# SAMD_Arduino_1.net
KiCad netlist of a schematic drawn in Altium Designer
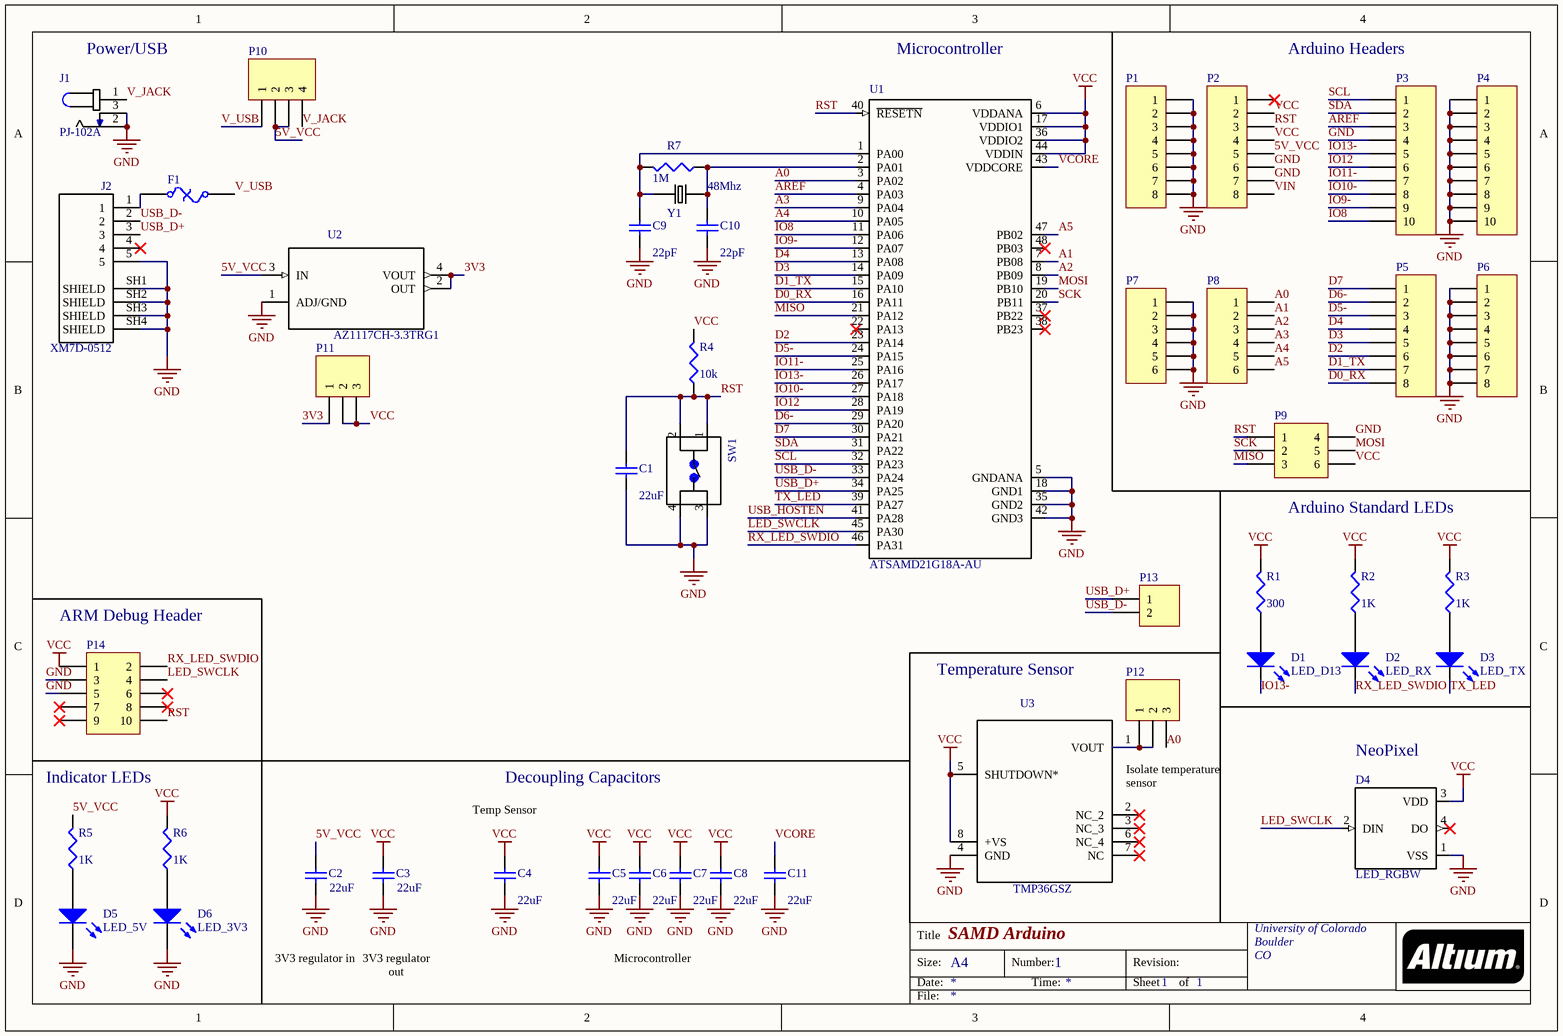
[diagram p0: SAMD_Arduino_1.SchDoc]

(export (version "E")
  (design (tool "Eeschema 10.0.6"))
  (components
    (comp (ref "C1")
      (value "22uF")
      (footprint "C1206")
      (description "Capacitor (Semiconductor SIM Model)")
      (fields (field (name "Comment") "Cap Semi") (field (name "PUBLISHER") "Altium Limited"))
      (libsource (lib "Miscellaneous Devices") (part "Cap Semi"))
    )
    (comp (ref "C2")
      (value "22uF")
      (footprint "C1206")
      (description "Capacitor (Semiconductor SIM Model)")
      (fields
        (field (name "DIGIKEYPARTNO") "1276-3300-1-ND")
        (field (name "Comment") "Cap Semi")
        (field (name "PUBLISHER") "Altium Limited")
      )
      (libsource (lib "Miscellaneous Devices") (part "Cap Semi"))
    )
    (comp (ref "C3")
      (value "22uF")
      (footprint "C1206")
      (description "Capacitor (Semiconductor SIM Model)")
      (fields
        (field (name "DIGIKEYPARTNO") "1276-3300-1-ND")
        (field (name "Comment") "Cap Semi")
        (field (name "PUBLISHER") "Altium Limited")
      )
      (libsource (lib "Miscellaneous Devices") (part "Cap Semi"))
    )
    (comp (ref "C4")
      (value "22uF")
      (footprint "C1206")
      (description "Capacitor (Semiconductor SIM Model)")
      (fields
        (field (name "DIGIKEYPARTNO") "1276-3300-1-ND")
        (field (name "Comment") "Cap Semi")
        (field (name "PUBLISHER") "Altium Limited")
      )
      (libsource (lib "Miscellaneous Devices") (part "Cap Semi"))
    )
    (comp (ref "C5")
      (value "22uF")
      (footprint "C1206")
      (description "Capacitor (Semiconductor SIM Model)")
      (fields
        (field (name "DIGIKEYPARTNO") "1276-3300-1-ND")
        (field (name "Comment") "Cap Semi")
        (field (name "PUBLISHER") "Altium Limited")
      )
      (libsource (lib "Miscellaneous Devices") (part "Cap Semi"))
    )
    (comp (ref "C6")
      (value "22uF")
      (footprint "C1206")
      (description "Capacitor (Semiconductor SIM Model)")
      (fields
        (field (name "DIGIKEYPARTNO") "1276-3300-1-ND")
        (field (name "Comment") "Cap Semi")
        (field (name "PUBLISHER") "Altium Limited")
      )
      (libsource (lib "Miscellaneous Devices") (part "Cap Semi"))
    )
    (comp (ref "C7")
      (value "22uF")
      (footprint "C1206")
      (description "Capacitor (Semiconductor SIM Model)")
      (fields
        (field (name "DIGIKEYPARTNO") "1276-3300-1-ND")
        (field (name "Comment") "Cap Semi")
        (field (name "PUBLISHER") "Altium Limited")
      )
      (libsource (lib "Miscellaneous Devices") (part "Cap Semi"))
    )
    (comp (ref "C8")
      (value "22uF")
      (footprint "C1206")
      (description "Capacitor (Semiconductor SIM Model)")
      (fields
        (field (name "DIGIKEYPARTNO") "1276-3300-1-ND")
        (field (name "Comment") "Cap Semi")
        (field (name "PUBLISHER") "Altium Limited")
      )
      (libsource (lib "Miscellaneous Devices") (part "Cap Semi"))
    )
    (comp (ref "C9")
      (value "22pF")
      (footprint "C1206")
      (description "Capacitor (Semiconductor SIM Model)")
      (fields
        (field (name "DIGIKEYPARTNO") "732-7867-1-ND")
        (field (name "Comment") "Cap Semi")
        (field (name "PUBLISHER") "Altium Limited")
      )
      (libsource (lib "Miscellaneous Devices") (part "Cap Semi"))
    )
    (comp (ref "C10")
      (value "22pF")
      (footprint "C1206")
      (description "Capacitor (Semiconductor SIM Model)")
      (fields
        (field (name "DIGIKEYPARTNO") "732-7867-1-ND")
        (field (name "Comment") "Cap Semi")
        (field (name "PUBLISHER") "Altium Limited")
      )
      (libsource (lib "Miscellaneous Devices") (part "Cap Semi"))
    )
    (comp (ref "C11")
      (value "22uF")
      (footprint "C1206")
      (description "Capacitor (Semiconductor SIM Model)")
      (fields
        (field (name "DIGIKEYPARTNO") "1276-3300-1-ND")
        (field (name "Comment") "Cap Semi")
        (field (name "PUBLISHER") "Altium Limited")
      )
      (libsource (lib "Miscellaneous Devices") (part "Cap Semi"))
    )
    (comp (ref "D1")
      (value "LED_D13")
      (footprint "3.2X1.6X1.1")
      (description "Typical RED, GREEN, YELLOW, AMBER GaAs LED")
      (fields (field (name "PUBLISHER") "Altium Limited"))
      (libsource (lib "Miscellaneous Devices") (part "LED2"))
    )
    (comp (ref "D2")
      (value "LED_RX")
      (footprint "3.2X1.6X1.1")
      (description "Typical RED, GREEN, YELLOW, AMBER GaAs LED")
      (fields (field (name "PUBLISHER") "Altium Limited"))
      (libsource (lib "Miscellaneous Devices") (part "LED2"))
    )
    (comp (ref "D3")
      (value "LED_TX")
      (footprint "3.2X1.6X1.1")
      (description "Typical RED, GREEN, YELLOW, AMBER GaAs LED")
      (fields (field (name "PUBLISHER") "Altium Limited"))
      (libsource (lib "Miscellaneous Devices") (part "LED2"))
    )
    (comp (ref "D4")
      (value "LED_RGBW")
      (footprint "*LED_IN-PI554FCH")
      (description "5050RGB with integrated IC built in 4 PIN Â•Viewing angle: 120 degrees")
      (fields (field (name "MP") "IN-PI554FCH") (field (name "MF") "Inolux"))
      (libsource (lib "IN-PI554FCH") (part "IN-PI554FCH"))
    )
    (comp (ref "D5")
      (value "LED_5V")
      (footprint "3.2X1.6X1.1")
      (description "Typical RED, GREEN, YELLOW, AMBER GaAs LED")
      (fields (field (name "PUBLISHER") "Altium Limited"))
      (libsource (lib "Miscellaneous Devices") (part "LED2"))
    )
    (comp (ref "D6")
      (value "LED_3V3")
      (footprint "3.2X1.6X1.1")
      (description "Typical RED, GREEN, YELLOW, AMBER GaAs LED")
      (fields (field (name "PUBLISHER") "Altium Limited"))
      (libsource (lib "Miscellaneous Devices") (part "LED2"))
    )
    (comp (ref "F1")
      (value "Fuse Thermal")
      (footprint "1812")
      (description "Thermal Fuse")
      (fields
        (field (name "MANUFACTURERPARTNO") "MF-MSMF050-2")
        (field (name "DIGIKEYPARTNO") "MF-MSMF050-2CT-ND")
        (field (name "PUBLISHER") "Altium Limited")
      )
      (libsource (lib "Miscellaneous Devices") (part "Fuse Thermal"))
    )
    (comp (ref "J1")
      (value "PJ-102A")
      (footprint "*CUI_PJ-102A")
      (description "2.0 mm Center Pin, 2.5 A, Right Angle, Through Hole, Tapered Pins, Dc Power Jack Connector")
      (fields (field (name "MF") "CUI Inc."))
      (libsource (lib "PJ-102A") (part "PJ-102A"))
    )
    (comp (ref "J2")
      (value "XM7D-0512")
      (footprint "*OMRON_XM7D-0512_XM7D-0512(Primary)")
      (description "Conn Mini USB Type B SKT 5 POS 0.8mm Solder RA Thru-Hole 5 Terminal 1 Port")
      (fields (field (name "MF") "Omron Electronics"))
      (libsource (lib "XM7D-0512") (part "XM7D-0512"))
    )
    (comp (ref "P1")
      (value "GND")
      (footprint "HDR1X8")
      (description "Header, 8-Pin")
      (fields (field (name "PUBLISHER") "Altium Limited"))
      (libsource (lib "Miscellaneous Connectors") (part "Header 8"))
    )
    (comp (ref "P2")
      (value "P4")
      (footprint "HDR1X8")
      (description "Header, 8-Pin")
      (fields (field (name "PUBLISHER") "Altium Limited"))
      (libsource (lib "Miscellaneous Connectors") (part "Header 8"))
    )
    (comp (ref "P3")
      (value "P1")
      (footprint "HDR1X10")
      (description "Header, 10-Pin")
      (fields (field (name "PUBLISHER") "Altium Limited"))
      (libsource (lib "Miscellaneous Connectors") (part "Header 10"))
    )
    (comp (ref "P4")
      (value "GND")
      (footprint "HDR1X10")
      (description "Header, 10-Pin")
      (fields (field (name "PUBLISHER") "Altium Limited"))
      (libsource (lib "Miscellaneous Connectors") (part "Header 10"))
    )
    (comp (ref "P5")
      (value "P2")
      (footprint "HDR1X8")
      (description "Header, 8-Pin")
      (fields (field (name "PUBLISHER") "Altium Limited"))
      (libsource (lib "") (part "Header 8_1"))
    )
    (comp (ref "P6")
      (value "GND")
      (footprint "HDR1X8")
      (description "Header, 8-Pin")
      (fields (field (name "PUBLISHER") "Altium Limited"))
      (libsource (lib "") (part "Header 8_1"))
    )
    (comp (ref "P7")
      (value "GND")
      (footprint "HDR1X6")
      (description "Header, 6-Pin")
      (fields (field (name "PUBLISHER") "Altium Limited"))
      (libsource (lib "Miscellaneous Connectors") (part "Header 6"))
    )
    (comp (ref "P8")
      (value "P3")
      (footprint "HDR1X6")
      (description "Header, 6-Pin")
      (fields (field (name "PUBLISHER") "Altium Limited"))
      (libsource (lib "Miscellaneous Connectors") (part "Header 6"))
    )
    (comp (ref "P9")
      (value "Header 3X2A")
      (footprint "HDR2X3_CEN")
      (description "Header, 3-Pin, Dual row")
      (fields (field (name "PUBLISHER") "Altium Limited"))
      (libsource (lib "Miscellaneous Connectors") (part "Header 3X2A"))
    )
    (comp (ref "P10")
      (value "Header 4")
      (footprint "HDR1X4")
      (description "Header, 4-Pin")
      (fields (field (name "PUBLISHER") "Altium Limited"))
      (libsource (lib "Miscellaneous Connectors") (part "Header 4"))
    )
    (comp (ref "P11")
      (value "3.3 NC")
      (footprint "HDR1X3")
      (description "Header, 3-Pin")
      (fields (field (name "PUBLISHER") "Altium Limited"))
      (libsource (lib "Miscellaneous Connectors") (part "Header 3"))
    )
    (comp (ref "P12")
      (value "NC A0")
      (footprint "HDR1X3")
      (description "Header, 3-Pin")
      (fields (field (name "PUBLISHER") "Altium Limited"))
      (libsource (lib "Miscellaneous Connectors") (part "Header 3"))
    )
    (comp (ref "P13")
      (value "Header 2")
      (footprint "HDR1X2")
      (description "Header, 2-Pin")
      (fields (field (name "PUBLISHER") "Altium Limited"))
      (libsource (lib "Miscellaneous Connectors") (part "Header 2"))
    )
    (comp (ref "P14")
      (value "Header 5X2")
      (footprint "HDR2X5")
      (description "Header, 5-Pin, Dual row")
      (fields (field (name "PUBLISHER") "Altium Limited"))
      (libsource (lib "Miscellaneous Connectors") (part "Header 5X2"))
    )
    (comp (ref "R1")
      (value "300")
      (footprint "C1206")
      (description "Resistor")
      (fields (field (name "Comment") "Res3") (field (name "PUBLISHER") "Altium Limited"))
      (libsource (lib "Miscellaneous Devices") (part "Res3"))
    )
    (comp (ref "R2")
      (value "1K")
      (footprint "C1206")
      (description "Resistor")
      (fields (field (name "Comment") "Res3") (field (name "PUBLISHER") "Altium Limited"))
      (libsource (lib "Miscellaneous Devices") (part "Res3"))
    )
    (comp (ref "R3")
      (value "1K")
      (footprint "C1206")
      (description "Resistor")
      (fields (field (name "Comment") "Res3") (field (name "PUBLISHER") "Altium Limited"))
      (libsource (lib "Miscellaneous Devices") (part "Res3"))
    )
    (comp (ref "R4")
      (value "10k")
      (footprint "C1206")
      (description "Resistor")
      (fields (field (name "Comment") "Res3") (field (name "PUBLISHER") "Altium Limited"))
      (libsource (lib "Miscellaneous Devices") (part "Res3"))
    )
    (comp (ref "R5")
      (value "1K")
      (footprint "C1206")
      (description "Resistor")
      (fields (field (name "Comment") "Res3") (field (name "PUBLISHER") "Altium Limited"))
      (libsource (lib "Miscellaneous Devices") (part "Res3"))
    )
    (comp (ref "R6")
      (value "1K")
      (footprint "C1206")
      (description "Resistor")
      (fields (field (name "Comment") "Res3") (field (name "PUBLISHER") "Altium Limited"))
      (libsource (lib "Miscellaneous Devices") (part "Res3"))
    )
    (comp (ref "R7")
      (value "1M")
      (footprint "C1206")
      (description "Resistor")
      (fields (field (name "Comment") "Res3") (field (name "PUBLISHER") "Altium Limited"))
      (libsource (lib "Miscellaneous Devices") (part "Res3"))
    )
    (comp (ref "SW1")
      (value "RESET")
      (footprint "*TE_FSM4JSMA")
      (description "FSM4JSMA=SMT,TACTILE,PB SWITCH")
      (fields (field (name "MF") "TE Connectivity") (field (name "MP") "FSM4JSMA"))
      (libsource (lib "FSM4JSMA") (part "FSM4JSMA"))
    )
    (comp (ref "U1")
      (value "ATSAMD21G18A-AU")
      (footprint "*QFP50P900X900X120-48N")
      (description "SAMD21G Series 256 kB Flash 32 kB SRAM 48 MHz 32-Bit Microcontroller - TQFP-48")
      (fields (field (name "MF") "Microchip"))
      (libsource (lib "ATSAMD21G18A-AU") (part "ATSAMD21G18A-AU"))
    )
    (comp (ref "U2")
      (value "AZ1117CH-3.3TRG1")
      (footprint "*SOT230P696X180-4N")
      (description "Voltage stabiliser; LDO, fixed; 3.3V; 0.8A; SOT223; SMD")
      (fields
        (field (name "MF") "Diodes Incorporated")
        (field (name "DIGIKEYPARTNO") "AZ1117CH-3.3TRG1DICT-ND")
      )
      (libsource (lib "LM1117MP-3.3") (part "LM1117MP-3.3"))
    )
    (comp (ref "U3")
      (value "TMP36GSZ")
      (footprint "*SOIC127P600X175-8N")
      (description "Temp Sensor Analog_Voltage_ Serial _2-Wire_ 8-Pin SOIC N Tube")
      (fields (field (name "MF") "Analog Devices"))
      (libsource (lib "TMP36GSZ") (part "TMP36GSZ"))
    )
    (comp (ref "Y1")
      (value "48Mhz")
      (footprint "*XTAL_ECS-35-17-5PX-TR")
      (description "Crystal 3.579545MHz Â±30ppm _Tol_ Â±50ppm _Stability_ 17pF FUND 150Ohm 2-Pin HC-49/USX SMD T/R")
      (fields (field (name "MF") "Abracon LLC") (field (name "MP") "ABLS-48.000MHZ-B2-T"))
      (libsource (lib "ECS-35-17-5PX-TR") (part "ECS-35-17-5PX-TR"))
    )
  )
  (nets
    (net (code "1") (name "/3V3") (class "Default")
      (node (ref "P11") (pin "1") (pinfunction "1_1") (pintype "passive"))
      (node (ref "U2") (pin "2") (pinfunction "OUT_2") (pintype "output"))
      (node (ref "U2") (pin "4") (pinfunction "VOUT_4") (pintype "output"))
    )
    (net (code "2") (name "/5V_VCC") (class "Default")
      (node (ref "C2") (pin "2") (pinfunction "2_2") (pintype "passive"))
      (node (ref "P10") (pin "2") (pinfunction "2_2") (pintype "passive"))
      (node (ref "P10") (pin "3") (pinfunction "3_3") (pintype "passive"))
      (node (ref "P2") (pin "5") (pinfunction "5_5") (pintype "passive"))
      (node (ref "R5") (pin "2") (pinfunction "2_2") (pintype "passive"))
      (node (ref "U2") (pin "3") (pinfunction "IN_3") (pintype "input"))
    )
    (net (code "3") (name "/A0") (class "Default")
      (node (ref "P12") (pin "3") (pinfunction "3_3") (pintype "passive"))
      (node (ref "P8") (pin "1") (pinfunction "1_1") (pintype "passive"))
      (node (ref "U1") (pin "3") (pinfunction "PA02_3") (pintype "bidirectional"))
    )
    (net (code "4") (name "/A1") (class "Default")
      (node (ref "P8") (pin "2") (pinfunction "2_2") (pintype "passive"))
      (node (ref "U1") (pin "7") (pinfunction "PB08_7") (pintype "bidirectional"))
    )
    (net (code "5") (name "/A2") (class "Default")
      (node (ref "P8") (pin "3") (pinfunction "3_3") (pintype "passive"))
      (node (ref "U1") (pin "8") (pinfunction "PB09_8") (pintype "bidirectional"))
    )
    (net (code "6") (name "/A3") (class "Default")
      (node (ref "P8") (pin "4") (pinfunction "4_4") (pintype "passive"))
      (node (ref "U1") (pin "9") (pinfunction "PA04_9") (pintype "bidirectional"))
    )
    (net (code "7") (name "/A4") (class "Default")
      (node (ref "P8") (pin "5") (pinfunction "5_5") (pintype "passive"))
      (node (ref "U1") (pin "10") (pinfunction "PA05_10") (pintype "bidirectional"))
    )
    (net (code "8") (name "/A5") (class "Default")
      (node (ref "P8") (pin "6") (pinfunction "6_6") (pintype "passive"))
      (node (ref "U1") (pin "47") (pinfunction "PB02_47") (pintype "bidirectional"))
    )
    (net (code "9") (name "/AREF") (class "Default")
      (node (ref "P3") (pin "3") (pinfunction "3_3") (pintype "passive"))
      (node (ref "U1") (pin "4") (pinfunction "PA03_4") (pintype "bidirectional"))
    )
    (net (code "10") (name "/D0_RX") (class "Default")
      (node (ref "P5") (pin "8") (pinfunction "8_8") (pintype "passive"))
      (node (ref "U1") (pin "16") (pinfunction "PA11_16") (pintype "bidirectional"))
    )
    (net (code "11") (name "/D1_TX") (class "Default")
      (node (ref "P5") (pin "7") (pinfunction "7_7") (pintype "passive"))
      (node (ref "U1") (pin "15") (pinfunction "PA10_15") (pintype "bidirectional"))
    )
    (net (code "12") (name "/D2") (class "Default")
      (node (ref "P5") (pin "6") (pinfunction "6_6") (pintype "passive"))
      (node (ref "U1") (pin "23") (pinfunction "PA14_23") (pintype "bidirectional"))
    )
    (net (code "13") (name "/D3") (class "Default")
      (node (ref "P5") (pin "5") (pinfunction "5_5") (pintype "passive"))
      (node (ref "U1") (pin "14") (pinfunction "PA09_14") (pintype "bidirectional"))
    )
    (net (code "14") (name "/D4") (class "Default")
      (node (ref "P5") (pin "4") (pinfunction "4_4") (pintype "passive"))
      (node (ref "U1") (pin "13") (pinfunction "PA08_13") (pintype "bidirectional"))
    )
    (net (code "15") (name "/D5-") (class "Default")
      (node (ref "P5") (pin "3") (pinfunction "3_3") (pintype "passive"))
      (node (ref "U1") (pin "24") (pinfunction "PA15_24") (pintype "bidirectional"))
    )
    (net (code "16") (name "/D6-") (class "Default")
      (node (ref "P5") (pin "2") (pinfunction "2_2") (pintype "passive"))
      (node (ref "U1") (pin "29") (pinfunction "PA20_29") (pintype "bidirectional"))
    )
    (net (code "17") (name "/D7") (class "Default")
      (node (ref "P5") (pin "1") (pinfunction "1_1") (pintype "passive"))
      (node (ref "U1") (pin "30") (pinfunction "PA21_30") (pintype "bidirectional"))
    )
    (net (code "18") (name "/IO8") (class "Default")
      (node (ref "P3") (pin "10") (pinfunction "10_10") (pintype "passive"))
      (node (ref "U1") (pin "11") (pinfunction "PA06_11") (pintype "bidirectional"))
    )
    (net (code "19") (name "/IO9-") (class "Default")
      (node (ref "P3") (pin "9") (pinfunction "9_9") (pintype "passive"))
      (node (ref "U1") (pin "12") (pinfunction "PA07_12") (pintype "bidirectional"))
    )
    (net (code "20") (name "/IO10-") (class "Default")
      (node (ref "P3") (pin "8") (pinfunction "8_8") (pintype "passive"))
      (node (ref "U1") (pin "27") (pinfunction "PA18_27") (pintype "bidirectional"))
    )
    (net (code "21") (name "/IO11-") (class "Default")
      (node (ref "P3") (pin "7") (pinfunction "7_7") (pintype "passive"))
      (node (ref "U1") (pin "25") (pinfunction "PA16_25") (pintype "bidirectional"))
    )
    (net (code "22") (name "/IO12") (class "Default")
      (node (ref "P3") (pin "6") (pinfunction "6_6") (pintype "passive"))
      (node (ref "U1") (pin "28") (pinfunction "PA19_28") (pintype "bidirectional"))
    )
    (net (code "23") (name "/IO13-") (class "Default")
      (node (ref "D1") (pin "2") (pinfunction "K_2") (pintype "passive"))
      (node (ref "P3") (pin "5") (pinfunction "5_5") (pintype "passive"))
      (node (ref "U1") (pin "26") (pinfunction "PA17_26") (pintype "bidirectional"))
    )
    (net (code "24") (name "/LED_SWCLK") (class "Default")
      (node (ref "D4") (pin "2") (pinfunction "DIN_2") (pintype "input"))
      (node (ref "P14") (pin "4") (pinfunction "4_4") (pintype "passive"))
      (node (ref "U1") (pin "45") (pinfunction "PA30_45") (pintype "bidirectional"))
    )
    (net (code "25") (name "/MISO") (class "Default")
      (node (ref "P9") (pin "3") (pinfunction "3_3") (pintype "passive"))
      (node (ref "U1") (pin "21") (pinfunction "PA12_21") (pintype "bidirectional"))
    )
    (net (code "26") (name "/MOSI") (class "Default")
      (node (ref "P9") (pin "5") (pinfunction "5_5") (pintype "passive"))
      (node (ref "U1") (pin "19") (pinfunction "PB10_19") (pintype "bidirectional"))
    )
    (net (code "27") (name "/RST") (class "Default")
      (node (ref "C1") (pin "2") (pinfunction "2_2") (pintype "passive"))
      (node (ref "P14") (pin "10") (pinfunction "10_10") (pintype "passive"))
      (node (ref "P2") (pin "3") (pinfunction "3_3") (pintype "passive"))
      (node (ref "P9") (pin "1") (pinfunction "1_1") (pintype "passive"))
      (node (ref "R4") (pin "1") (pinfunction "1_1") (pintype "passive"))
      (node (ref "SW1") (pin "1") (pinfunction "1_1") (pintype "passive"))
      (node (ref "SW1") (pin "2") (pinfunction "2_2") (pintype "passive"))
      (node (ref "U1") (pin "40") (pinfunction "~{RESETN}_40") (pintype "input"))
    )
    (net (code "28") (name "/RX_LED_SWDIO") (class "Default")
      (node (ref "D2") (pin "2") (pinfunction "K_2") (pintype "passive"))
      (node (ref "P14") (pin "2") (pinfunction "2_2") (pintype "passive"))
      (node (ref "U1") (pin "46") (pinfunction "PA31_46") (pintype "bidirectional"))
    )
    (net (code "29") (name "/SCK") (class "Default")
      (node (ref "P9") (pin "2") (pinfunction "2_2") (pintype "passive"))
      (node (ref "U1") (pin "20") (pinfunction "PB11_20") (pintype "bidirectional"))
    )
    (net (code "30") (name "/SCL") (class "Default")
      (node (ref "P3") (pin "1") (pinfunction "1_1") (pintype "passive"))
      (node (ref "U1") (pin "32") (pinfunction "PA23_32") (pintype "bidirectional"))
    )
    (net (code "31") (name "/SDA") (class "Default")
      (node (ref "P3") (pin "2") (pinfunction "2_2") (pintype "passive"))
      (node (ref "U1") (pin "31") (pinfunction "PA22_31") (pintype "bidirectional"))
    )
    (net (code "32") (name "/TX_LED") (class "Default")
      (node (ref "D3") (pin "2") (pinfunction "K_2") (pintype "passive"))
      (node (ref "U1") (pin "39") (pinfunction "PA27_39") (pintype "bidirectional"))
    )
    (net (code "33") (name "/USB_D+") (class "Default")
      (node (ref "J2") (pin "3") (pinfunction "3_3") (pintype "passive"))
      (node (ref "P13") (pin "1") (pinfunction "1_1") (pintype "passive"))
      (node (ref "U1") (pin "34") (pinfunction "PA25_34") (pintype "bidirectional"))
    )
    (net (code "34") (name "/USB_D-") (class "Default")
      (node (ref "J2") (pin "2") (pinfunction "2_2") (pintype "passive"))
      (node (ref "P13") (pin "2") (pinfunction "2_2") (pintype "passive"))
      (node (ref "U1") (pin "33") (pinfunction "PA24_33") (pintype "bidirectional"))
    )
    (net (code "35") (name "/USB_HOSTEN") (class "Default")
      (node (ref "U1") (pin "41") (pinfunction "PA28_41") (pintype "bidirectional"))
    )
    (net (code "36") (name "/VCORE") (class "Default")
      (node (ref "C11") (pin "2") (pinfunction "2_2") (pintype "passive"))
      (node (ref "U1") (pin "43") (pinfunction "VDDCORE_43") (pintype "power_in"))
    )
    (net (code "37") (name "/VIN") (class "Default")
      (node (ref "P2") (pin "8") (pinfunction "8_8") (pintype "passive"))
    )
    (net (code "38") (name "/V_JACK") (class "Default")
      (node (ref "J1") (pin "1") (pinfunction "1_1") (pintype "passive"))
      (node (ref "P10") (pin "4") (pinfunction "4_4") (pintype "passive"))
    )
    (net (code "39") (name "/V_USB") (class "Default")
      (node (ref "F1") (pin "2") (pinfunction "2_2") (pintype "passive"))
      (node (ref "P10") (pin "1") (pinfunction "1_1") (pintype "passive"))
    )
    (net (code "40") (name "GND") (class "Default")
      (node (ref "C1") (pin "1") (pinfunction "1_1") (pintype "passive"))
      (node (ref "C10") (pin "1") (pinfunction "1_1") (pintype "passive"))
      (node (ref "C11") (pin "1") (pinfunction "1_1") (pintype "passive"))
      (node (ref "C2") (pin "1") (pinfunction "1_1") (pintype "passive"))
      (node (ref "C3") (pin "1") (pinfunction "1_1") (pintype "passive"))
      (node (ref "C4") (pin "1") (pinfunction "1_1") (pintype "passive"))
      (node (ref "C5") (pin "1") (pinfunction "1_1") (pintype "passive"))
      (node (ref "C6") (pin "1") (pinfunction "1_1") (pintype "passive"))
      (node (ref "C7") (pin "1") (pinfunction "1_1") (pintype "passive"))
      (node (ref "C8") (pin "1") (pinfunction "1_1") (pintype "passive"))
      (node (ref "C9") (pin "1") (pinfunction "1_1") (pintype "passive"))
      (node (ref "D4") (pin "1") (pinfunction "VSS_1") (pintype "power_in"))
      (node (ref "D5") (pin "2") (pinfunction "K_2") (pintype "passive"))
      (node (ref "D6") (pin "2") (pinfunction "K_2") (pintype "passive"))
      (node (ref "J1") (pin "2") (pinfunction "2_2") (pintype "passive"))
      (node (ref "J1") (pin "3") (pinfunction "3_3") (pintype "passive"))
      (node (ref "J2") (pin "5") (pinfunction "5_5") (pintype "passive"))
      (node (ref "J2") (pin "SH1") (pinfunction "SHIELD_SH1") (pintype "passive"))
      (node (ref "J2") (pin "SH2") (pinfunction "SHIELD_SH2") (pintype "passive"))
      (node (ref "J2") (pin "SH3") (pinfunction "SHIELD_SH3") (pintype "passive"))
      (node (ref "J2") (pin "SH4") (pinfunction "SHIELD_SH4") (pintype "passive"))
      (node (ref "P1") (pin "1") (pinfunction "1_1") (pintype "passive"))
      (node (ref "P1") (pin "2") (pinfunction "2_2") (pintype "passive"))
      (node (ref "P1") (pin "3") (pinfunction "3_3") (pintype "passive"))
      (node (ref "P1") (pin "4") (pinfunction "4_4") (pintype "passive"))
      (node (ref "P1") (pin "5") (pinfunction "5_5") (pintype "passive"))
      (node (ref "P1") (pin "6") (pinfunction "6_6") (pintype "passive"))
      (node (ref "P1") (pin "7") (pinfunction "7_7") (pintype "passive"))
      (node (ref "P1") (pin "8") (pinfunction "8_8") (pintype "passive"))
      (node (ref "P14") (pin "3") (pinfunction "3_3") (pintype "passive"))
      (node (ref "P14") (pin "5") (pinfunction "5_5") (pintype "passive"))
      (node (ref "P2") (pin "6") (pinfunction "6_6") (pintype "passive"))
      (node (ref "P2") (pin "7") (pinfunction "7_7") (pintype "passive"))
      (node (ref "P3") (pin "4") (pinfunction "4_4") (pintype "passive"))
      (node (ref "P4") (pin "1") (pinfunction "1_1") (pintype "passive"))
      (node (ref "P4") (pin "10") (pinfunction "10_10") (pintype "passive"))
      (node (ref "P4") (pin "2") (pinfunction "2_2") (pintype "passive"))
      (node (ref "P4") (pin "3") (pinfunction "3_3") (pintype "passive"))
      (node (ref "P4") (pin "4") (pinfunction "4_4") (pintype "passive"))
      (node (ref "P4") (pin "5") (pinfunction "5_5") (pintype "passive"))
      (node (ref "P4") (pin "6") (pinfunction "6_6") (pintype "passive"))
      (node (ref "P4") (pin "7") (pinfunction "7_7") (pintype "passive"))
      (node (ref "P4") (pin "8") (pinfunction "8_8") (pintype "passive"))
      (node (ref "P4") (pin "9") (pinfunction "9_9") (pintype "passive"))
      (node (ref "P6") (pin "1") (pinfunction "1_1") (pintype "passive"))
      (node (ref "P6") (pin "2") (pinfunction "2_2") (pintype "passive"))
      (node (ref "P6") (pin "3") (pinfunction "3_3") (pintype "passive"))
      (node (ref "P6") (pin "4") (pinfunction "4_4") (pintype "passive"))
      (node (ref "P6") (pin "5") (pinfunction "5_5") (pintype "passive"))
      (node (ref "P6") (pin "6") (pinfunction "6_6") (pintype "passive"))
      (node (ref "P6") (pin "7") (pinfunction "7_7") (pintype "passive"))
      (node (ref "P6") (pin "8") (pinfunction "8_8") (pintype "passive"))
      (node (ref "P7") (pin "1") (pinfunction "1_1") (pintype "passive"))
      (node (ref "P7") (pin "2") (pinfunction "2_2") (pintype "passive"))
      (node (ref "P7") (pin "3") (pinfunction "3_3") (pintype "passive"))
      (node (ref "P7") (pin "4") (pinfunction "4_4") (pintype "passive"))
      (node (ref "P7") (pin "5") (pinfunction "5_5") (pintype "passive"))
      (node (ref "P7") (pin "6") (pinfunction "6_6") (pintype "passive"))
      (node (ref "P9") (pin "4") (pinfunction "4_4") (pintype "passive"))
      (node (ref "SW1") (pin "3") (pinfunction "3_3") (pintype "passive"))
      (node (ref "SW1") (pin "4") (pinfunction "4_4") (pintype "passive"))
      (node (ref "U1") (pin "18") (pinfunction "GND1_18") (pintype "power_in"))
      (node (ref "U1") (pin "35") (pinfunction "GND2_35") (pintype "power_in"))
      (node (ref "U1") (pin "42") (pinfunction "GND3_42") (pintype "power_in"))
      (node (ref "U1") (pin "5") (pinfunction "GNDANA_5") (pintype "power_in"))
      (node (ref "U2") (pin "1") (pinfunction "ADJ/GND_1") (pintype "passive"))
      (node (ref "U3") (pin "4") (pinfunction "GND_4") (pintype "passive"))
    )
    (net (code "41") (name "Net-(D1-A)") (class "Default")
      (node (ref "D1") (pin "1") (pinfunction "A_1") (pintype "passive"))
      (node (ref "R1") (pin "1") (pinfunction "1_1") (pintype "passive"))
    )
    (net (code "42") (name "Net-(D2-A)") (class "Default")
      (node (ref "D2") (pin "1") (pinfunction "A_1") (pintype "passive"))
      (node (ref "R2") (pin "1") (pinfunction "1_1") (pintype "passive"))
    )
    (net (code "43") (name "Net-(D3-A)") (class "Default")
      (node (ref "D3") (pin "1") (pinfunction "A_1") (pintype "passive"))
      (node (ref "R3") (pin "1") (pinfunction "1_1") (pintype "passive"))
    )
    (net (code "44") (name "Net-(D5-A)") (class "Default")
      (node (ref "D5") (pin "1") (pinfunction "A_1") (pintype "passive"))
      (node (ref "R5") (pin "1") (pinfunction "1_1") (pintype "passive"))
    )
    (net (code "45") (name "Net-(D6-A)") (class "Default")
      (node (ref "D6") (pin "1") (pinfunction "A_1") (pintype "passive"))
      (node (ref "R6") (pin "1") (pinfunction "1_1") (pintype "passive"))
    )
    (net (code "46") (name "Net-(F1-Pad1)") (class "Default")
      (node (ref "F1") (pin "1") (pinfunction "1_1") (pintype "passive"))
      (node (ref "J2") (pin "1") (pinfunction "1_1") (pintype "passive"))
    )
    (net (code "47") (name "Net-(U1-PA00)") (class "Default")
      (node (ref "C9") (pin "2") (pinfunction "2_2") (pintype "passive"))
      (node (ref "R7") (pin "2") (pinfunction "2_2") (pintype "passive"))
      (node (ref "U1") (pin "1") (pinfunction "PA00_1") (pintype "bidirectional"))
      (node (ref "Y1") (pin "1") (pinfunction "1_1") (pintype "passive"))
    )
    (net (code "48") (name "Net-(U1-PA01)") (class "Default")
      (node (ref "C10") (pin "2") (pinfunction "2_2") (pintype "passive"))
      (node (ref "R7") (pin "1") (pinfunction "1_1") (pintype "passive"))
      (node (ref "U1") (pin "2") (pinfunction "PA01_2") (pintype "bidirectional"))
      (node (ref "Y1") (pin "2") (pinfunction "2_2") (pintype "passive"))
    )
    (net (code "49") (name "Net-(U3-VOUT)") (class "Default")
      (node (ref "P12") (pin "1") (pinfunction "1_1") (pintype "passive"))
      (node (ref "P12") (pin "2") (pinfunction "2_2") (pintype "passive"))
      (node (ref "U3") (pin "1") (pinfunction "VOUT_1") (pintype "passive"))
    )
    (net (code "50") (name "VCC") (class "Default")
      (node (ref "C3") (pin "2") (pinfunction "2_2") (pintype "passive"))
      (node (ref "C4") (pin "2") (pinfunction "2_2") (pintype "passive"))
      (node (ref "C5") (pin "2") (pinfunction "2_2") (pintype "passive"))
      (node (ref "C6") (pin "2") (pinfunction "2_2") (pintype "passive"))
      (node (ref "C7") (pin "2") (pinfunction "2_2") (pintype "passive"))
      (node (ref "C8") (pin "2") (pinfunction "2_2") (pintype "passive"))
      (node (ref "D4") (pin "3") (pinfunction "VDD_3") (pintype "power_in"))
      (node (ref "P11") (pin "2") (pinfunction "2_2") (pintype "passive"))
      (node (ref "P11") (pin "3") (pinfunction "3_3") (pintype "passive"))
      (node (ref "P14") (pin "1") (pinfunction "1_1") (pintype "passive"))
      (node (ref "P2") (pin "2") (pinfunction "2_2") (pintype "passive"))
      (node (ref "P2") (pin "4") (pinfunction "4_4") (pintype "passive"))
      (node (ref "P9") (pin "6") (pinfunction "6_6") (pintype "passive"))
      (node (ref "R1") (pin "2") (pinfunction "2_2") (pintype "passive"))
      (node (ref "R2") (pin "2") (pinfunction "2_2") (pintype "passive"))
      (node (ref "R3") (pin "2") (pinfunction "2_2") (pintype "passive"))
      (node (ref "R4") (pin "2") (pinfunction "2_2") (pintype "passive"))
      (node (ref "R6") (pin "2") (pinfunction "2_2") (pintype "passive"))
      (node (ref "U1") (pin "17") (pinfunction "VDDIO1_17") (pintype "power_in"))
      (node (ref "U1") (pin "36") (pinfunction "VDDIO2_36") (pintype "power_in"))
      (node (ref "U1") (pin "44") (pinfunction "VDDIN_44") (pintype "power_in"))
      (node (ref "U1") (pin "6") (pinfunction "VDDANA_6") (pintype "power_in"))
      (node (ref "U3") (pin "5") (pinfunction "SHUTDOWN*_5") (pintype "passive"))
      (node (ref "U3") (pin "8") (pinfunction "+VS_8") (pintype "power_in"))
    )
    (net (code "51") (name "unconnected-(D4-DO-Pad4)") (class "Default")
      (node (ref "D4") (pin "4") (pinfunction "DO_4") (pintype "output+no_connect"))
    )
    (net (code "52") (name "unconnected-(J2-Pad4)") (class "Default")
      (node (ref "J2") (pin "4") (pinfunction "4_4") (pintype "passive+no_connect"))
    )
    (net (code "53") (name "unconnected-(P2-Pad1)") (class "Default")
      (node (ref "P2") (pin "1") (pinfunction "1_1") (pintype "passive+no_connect"))
    )
    (net (code "54") (name "unconnected-(P14-Pad6)") (class "Default")
      (node (ref "P14") (pin "6") (pinfunction "6_6") (pintype "passive+no_connect"))
    )
    (net (code "55") (name "unconnected-(P14-Pad7)") (class "Default")
      (node (ref "P14") (pin "7") (pinfunction "7_7") (pintype "passive+no_connect"))
    )
    (net (code "56") (name "unconnected-(P14-Pad8)") (class "Default")
      (node (ref "P14") (pin "8") (pinfunction "8_8") (pintype "passive+no_connect"))
    )
    (net (code "57") (name "unconnected-(P14-Pad9)") (class "Default")
      (node (ref "P14") (pin "9") (pinfunction "9_9") (pintype "passive+no_connect"))
    )
    (net (code "58") (name "unconnected-(U1-PA13-Pad22)") (class "Default")
      (node (ref "U1") (pin "22") (pinfunction "PA13_22") (pintype "bidirectional+no_connect"))
    )
    (net (code "59") (name "unconnected-(U1-PB03-Pad48)") (class "Default")
      (node (ref "U1") (pin "48") (pinfunction "PB03_48") (pintype "bidirectional+no_connect"))
    )
    (net (code "60") (name "unconnected-(U1-PB22-Pad37)") (class "Default")
      (node (ref "U1") (pin "37") (pinfunction "PB22_37") (pintype "bidirectional+no_connect"))
    )
    (net (code "61") (name "unconnected-(U1-PB23-Pad38)") (class "Default")
      (node (ref "U1") (pin "38") (pinfunction "PB23_38") (pintype "bidirectional+no_connect"))
    )
    (net (code "62") (name "unconnected-(U3-NC-Pad7)") (class "Default")
      (node (ref "U3") (pin "7") (pinfunction "NC_7") (pintype "passive+no_connect"))
    )
    (net (code "63") (name "unconnected-(U3-NC_2-Pad2)") (class "Default")
      (node (ref "U3") (pin "2") (pinfunction "NC_2_2") (pintype "passive+no_connect"))
    )
    (net (code "64") (name "unconnected-(U3-NC_3-Pad3)") (class "Default")
      (node (ref "U3") (pin "3") (pinfunction "NC_3_3") (pintype "passive+no_connect"))
    )
    (net (code "65") (name "unconnected-(U3-NC_4-Pad6)") (class "Default")
      (node (ref "U3") (pin "6") (pinfunction "NC_4_6") (pintype "passive+no_connect"))
    )
  )
)
